# SCH.net
KiCad netlist of a schematic drawn in Altium Designer
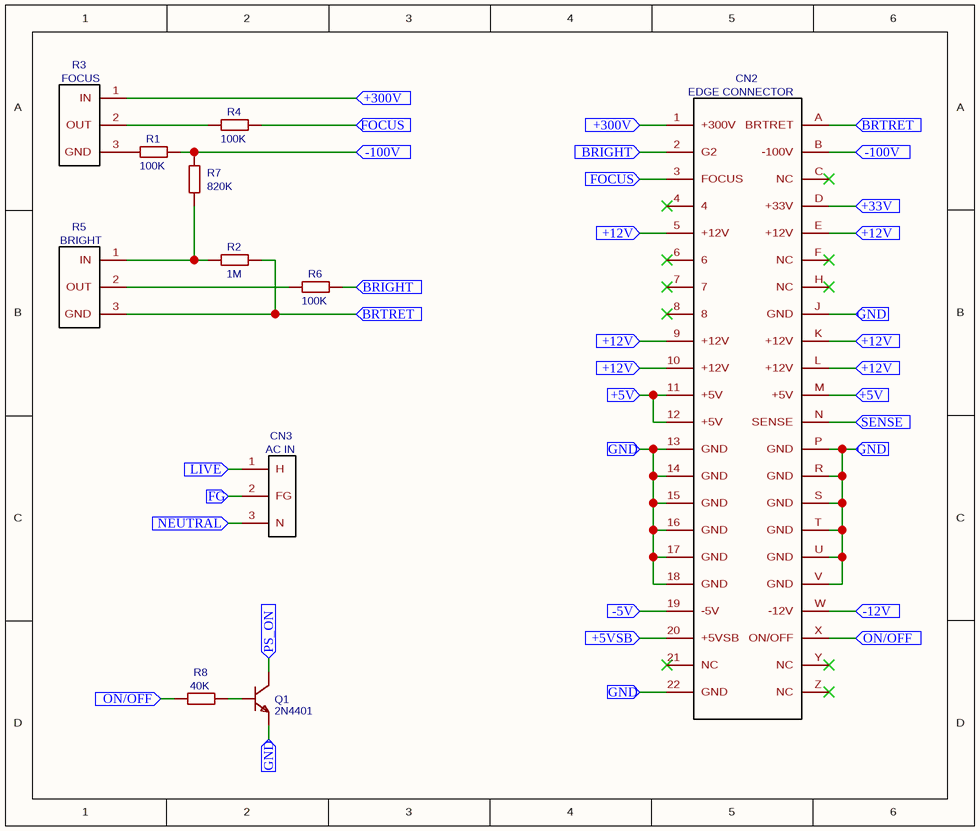
[diagram p0: SCH.schdoc]

(export (version "E")
  (design (tool "Eeschema 10.0.6"))
  (components
    (comp (ref "CN2")
      (value "EDGE CONNECTOR")
      (fields (field (name "CONTRIBUTOR") "will_tooker"))
      (libsource (lib "altium-import") (part "root_0_EDGE CONNECTOR_"))
    )
    (comp (ref "CN3")
      (value "AC IN")
      (fields (field (name "CONTRIBUTOR") "William Tooker"))
      (libsource (lib "altium-import") (part "root_0_AC IN_"))
    )
    (comp (ref "Q1")
      (value "2N4401")
      (fields (field (name "BOM_SUPPLIER PART") "C118540") (field (name "CONTRIBUTOR") "立创EDA官方封装库"))
      (libsource (lib "altium-import") (part "root_0_2N4401_"))
    )
    (comp (ref "R1")
      (value "100K")
      (fields (field (name "CONTRIBUTOR") "William Tooker"))
      (libsource (lib "altium-import") (part "root_0_100K_"))
    )
    (comp (ref "R2")
      (value "1M")
      (fields (field (name "CONTRIBUTOR") "William Tooker"))
      (libsource (lib "altium-import") (part "root_2_1M_"))
    )
    (comp (ref "R3")
      (value "FOCUS")
      (fields (field (name "CONTRIBUTOR") "William Tooker"))
      (libsource (lib "altium-import") (part "root_0_FOCUS_"))
    )
    (comp (ref "R4")
      (value "100K")
      (fields (field (name "CONTRIBUTOR") "William Tooker"))
      (libsource (lib "altium-import") (part "root_2_100K_"))
    )
    (comp (ref "R5")
      (value "BRIGHT")
      (fields (field (name "CONTRIBUTOR") "William Tooker"))
      (libsource (lib "altium-import") (part "root_0_BRIGHT_"))
    )
    (comp (ref "R6")
      (value "100K")
      (fields (field (name "CONTRIBUTOR") "William Tooker"))
      (libsource (lib "altium-import") (part "root_2_100K_"))
    )
    (comp (ref "R7")
      (value "820K")
      (fields (field (name "CONTRIBUTOR") "William Tooker"))
      (libsource (lib "altium-import") (part "root_3_820K_"))
    )
    (comp (ref "R8")
      (value "40K")
      (fields (field (name "CONTRIBUTOR") "William Tooker"))
      (libsource (lib "altium-import") (part "root_0_40K_"))
    )
  )
  (nets
    (net (code "1") (name "/+5V") (class "Default")
      (node (ref "CN2") (pin "11") (pinfunction "+5V_11") (pintype "passive"))
      (node (ref "CN2") (pin "12") (pinfunction "+5V_12") (pintype "passive"))
      (node (ref "CN2") (pin "M") (pinfunction "+5V_M") (pintype "passive"))
    )
    (net (code "2") (name "/+5VSB") (class "Default")
      (node (ref "CN2") (pin "20") (pinfunction "+5VSB_20") (pintype "passive"))
    )
    (net (code "3") (name "/+12V") (class "Default")
      (node (ref "CN2") (pin "10") (pinfunction "+12V_10") (pintype "passive"))
      (node (ref "CN2") (pin "5") (pinfunction "+12V_5") (pintype "passive"))
      (node (ref "CN2") (pin "9") (pinfunction "+12V_9") (pintype "passive"))
      (node (ref "CN2") (pin "E") (pinfunction "+12V_E") (pintype "passive"))
      (node (ref "CN2") (pin "K") (pinfunction "+12V_K") (pintype "passive"))
      (node (ref "CN2") (pin "L") (pinfunction "+12V_L") (pintype "passive"))
    )
    (net (code "4") (name "/+33V") (class "Default")
      (node (ref "CN2") (pin "D") (pinfunction "+33V_D") (pintype "passive"))
    )
    (net (code "5") (name "/+300V") (class "Default")
      (node (ref "CN2") (pin "1") (pinfunction "+300V_1") (pintype "passive"))
      (node (ref "R3") (pin "1") (pinfunction "IN_1") (pintype "passive"))
    )
    (net (code "6") (name "/-5V") (class "Default")
      (node (ref "CN2") (pin "19") (pinfunction "-5V_19") (pintype "passive"))
    )
    (net (code "7") (name "/-12V") (class "Default")
      (node (ref "CN2") (pin "W") (pinfunction "-12V_W") (pintype "passive"))
    )
    (net (code "8") (name "/-100V") (class "Default")
      (node (ref "CN2") (pin "B") (pinfunction "-100V_B") (pintype "passive"))
      (node (ref "R1") (pin "2") (pinfunction "2_2") (pintype "passive"))
      (node (ref "R7") (pin "1") (pinfunction "1_1") (pintype "passive"))
    )
    (net (code "9") (name "/BRIGHT") (class "Default")
      (node (ref "CN2") (pin "2") (pinfunction "G2_2") (pintype "passive"))
      (node (ref "R6") (pin "1") (pinfunction "1_1") (pintype "passive"))
    )
    (net (code "10") (name "/BRTRET") (class "Default")
      (node (ref "CN2") (pin "A") (pinfunction "BRTRET_A") (pintype "passive"))
      (node (ref "R2") (pin "1") (pinfunction "1_1") (pintype "passive"))
      (node (ref "R5") (pin "3") (pinfunction "GND_3") (pintype "passive"))
    )
    (net (code "11") (name "/FG") (class "Default")
      (node (ref "CN3") (pin "2") (pinfunction "FG_2") (pintype "passive"))
    )
    (net (code "12") (name "/FOCUS") (class "Default")
      (node (ref "CN2") (pin "3") (pinfunction "FOCUS_3") (pintype "passive"))
      (node (ref "R4") (pin "1") (pinfunction "1_1") (pintype "passive"))
    )
    (net (code "13") (name "/GND") (class "Default")
      (node (ref "CN2") (pin "13") (pinfunction "GND_13") (pintype "passive"))
      (node (ref "CN2") (pin "14") (pinfunction "GND_14") (pintype "passive"))
      (node (ref "CN2") (pin "15") (pinfunction "GND_15") (pintype "passive"))
      (node (ref "CN2") (pin "16") (pinfunction "GND_16") (pintype "passive"))
      (node (ref "CN2") (pin "17") (pinfunction "GND_17") (pintype "passive"))
      (node (ref "CN2") (pin "18") (pinfunction "GND_18") (pintype "passive"))
      (node (ref "CN2") (pin "22") (pinfunction "GND_22") (pintype "passive"))
      (node (ref "CN2") (pin "J") (pinfunction "GND_J") (pintype "passive"))
      (node (ref "CN2") (pin "P") (pinfunction "GND_P") (pintype "passive"))
      (node (ref "CN2") (pin "R") (pinfunction "GND_R") (pintype "passive"))
      (node (ref "CN2") (pin "S") (pinfunction "GND_S") (pintype "passive"))
      (node (ref "CN2") (pin "T") (pinfunction "GND_T") (pintype "passive"))
      (node (ref "CN2") (pin "U") (pinfunction "GND_U") (pintype "passive"))
      (node (ref "CN2") (pin "V") (pinfunction "GND_V") (pintype "passive"))
      (node (ref "Q1") (pin "1") (pinfunction "E_1") (pintype "passive"))
    )
    (net (code "14") (name "/LIVE") (class "Default")
      (node (ref "CN3") (pin "1") (pinfunction "H_1") (pintype "passive"))
    )
    (net (code "15") (name "/NEUTRAL") (class "Default")
      (node (ref "CN3") (pin "3") (pinfunction "N_3") (pintype "passive"))
    )
    (net (code "16") (name "/ON{slash}OFF") (class "Default")
      (node (ref "CN2") (pin "X") (pinfunction "ON/OFF_X") (pintype "passive"))
      (node (ref "R8") (pin "1") (pinfunction "1_1") (pintype "passive"))
    )
    (net (code "17") (name "/PS_ON") (class "Default")
      (node (ref "Q1") (pin "3") (pinfunction "C_3") (pintype "passive"))
    )
    (net (code "18") (name "/SENSE") (class "Default")
      (node (ref "CN2") (pin "N") (pinfunction "SENSE_N") (pintype "passive"))
    )
    (net (code "19") (name "Net-(Q1-B)") (class "Default")
      (node (ref "Q1") (pin "2") (pinfunction "B_2") (pintype "passive"))
      (node (ref "R8") (pin "2") (pinfunction "2_2") (pintype "passive"))
    )
    (net (code "20") (name "Net-(R3-GND)") (class "Default")
      (node (ref "R1") (pin "1") (pinfunction "1_1") (pintype "passive"))
      (node (ref "R3") (pin "3") (pinfunction "GND_3") (pintype "passive"))
    )
    (net (code "21") (name "Net-(R3-OUT)") (class "Default")
      (node (ref "R3") (pin "2") (pinfunction "OUT_2") (pintype "passive"))
      (node (ref "R4") (pin "2") (pinfunction "2_2") (pintype "passive"))
    )
    (net (code "22") (name "Net-(R5-IN)") (class "Default")
      (node (ref "R2") (pin "2") (pinfunction "2_2") (pintype "passive"))
      (node (ref "R5") (pin "1") (pinfunction "IN_1") (pintype "passive"))
      (node (ref "R7") (pin "2") (pinfunction "2_2") (pintype "passive"))
    )
    (net (code "23") (name "Net-(R5-OUT)") (class "Default")
      (node (ref "R5") (pin "2") (pinfunction "OUT_2") (pintype "passive"))
      (node (ref "R6") (pin "2") (pinfunction "2_2") (pintype "passive"))
    )
    (net (code "24") (name "unconnected-(CN2-NC-Pad21)") (class "Default")
      (node (ref "CN2") (pin "21") (pinfunction "NC_21") (pintype "passive+no_connect"))
    )
    (net (code "25") (name "unconnected-(CN2-NC-PadC)") (class "Default")
      (node (ref "CN2") (pin "C") (pinfunction "NC_C") (pintype "passive+no_connect"))
    )
    (net (code "26") (name "unconnected-(CN2-NC-PadF)") (class "Default")
      (node (ref "CN2") (pin "F") (pinfunction "NC_F") (pintype "passive+no_connect"))
    )
    (net (code "27") (name "unconnected-(CN2-NC-PadH)") (class "Default")
      (node (ref "CN2") (pin "H") (pinfunction "NC_H") (pintype "passive+no_connect"))
    )
    (net (code "28") (name "unconnected-(CN2-NC-PadY)") (class "Default")
      (node (ref "CN2") (pin "Y") (pinfunction "NC_Y") (pintype "passive+no_connect"))
    )
    (net (code "29") (name "unconnected-(CN2-NC-PadZ)") (class "Default")
      (node (ref "CN2") (pin "Z") (pinfunction "NC_Z") (pintype "passive+no_connect"))
    )
    (net (code "30") (name "unconnected-(CN2-Pad4)") (class "Default")
      (node (ref "CN2") (pin "4") (pinfunction "4_4") (pintype "passive+no_connect"))
    )
    (net (code "31") (name "unconnected-(CN2-Pad6)") (class "Default")
      (node (ref "CN2") (pin "6") (pinfunction "6_6") (pintype "passive+no_connect"))
    )
    (net (code "32") (name "unconnected-(CN2-Pad7)") (class "Default")
      (node (ref "CN2") (pin "7") (pinfunction "7_7") (pintype "passive+no_connect"))
    )
    (net (code "33") (name "unconnected-(CN2-Pad8)") (class "Default")
      (node (ref "CN2") (pin "8") (pinfunction "8_8") (pintype "passive+no_connect"))
    )
  )
)
